# LED_Driver_AREM-80C0.net
KiCad netlist of a schematic drawn in Altium Designer
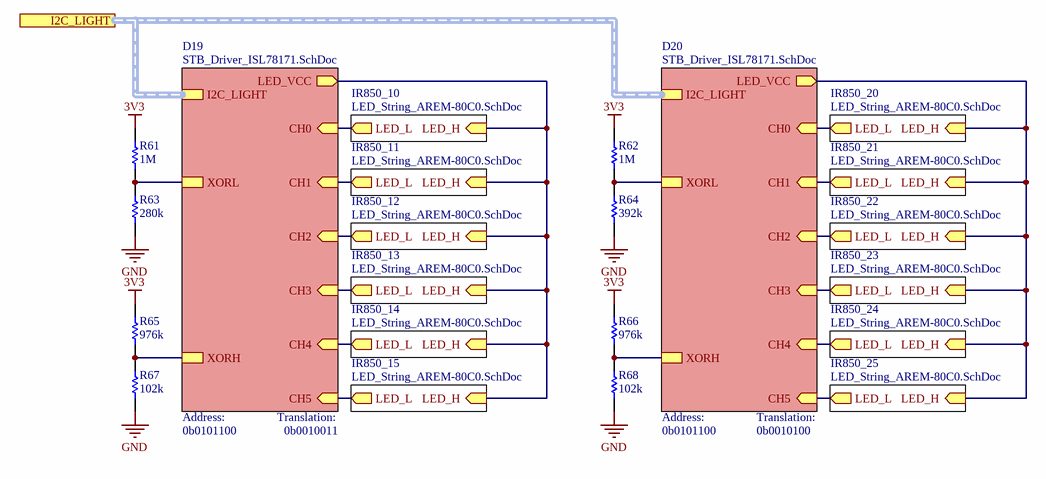
[diagram p0: LED_Driver_AREM-80C0.SchDoc]

(export (version "E")
  (design (tool "Eeschema 10.0.6"))
  (components
    (comp (ref "R61")
      (value "1M")
      (footprint "RESC1005X40X25LL05T05")
      (description "Chip Resistor, 1 MOhm, +/- 1%, 100 mW, -55 to 155 degC, 0402 (1005 Metric), RoHS, Tape and Reel")
      (fields (field (name "PARTNUMBER") "ERJ-2RKF1004X") (field (name "TOLERANCE") "1%"))
      (libsource (lib "Altium Content Vault") (part "RES-2"))
    )
    (comp (ref "R62")
      (value "1M")
      (footprint "RESC1005X40X25LL05T05")
      (description "Chip Resistor, 1 MOhm, +/- 1%, 100 mW, -55 to 155 degC, 0402 (1005 Metric), RoHS, Tape and Reel")
      (fields (field (name "PARTNUMBER") "ERJ-2RKF1004X") (field (name "TOLERANCE") "1%"))
      (libsource (lib "Altium Content Vault") (part "RES-2"))
    )
    (comp (ref "R63")
      (value "280k")
      (footprint "RESC1005X40X25LL05T05")
      (description "Chip Resistor, 280 KOhm, +/- 1%, 100 mW, -55 to 155 degC, 0402 (1005 Metric), RoHS, Cut Tape")
      (fields (field (name "PARTNUMBER") "ERJ-2RKF2803X") (field (name "MANUFACTURER") "Basic Passives"))
      (libsource (lib "Altium Content Vault") (part "RES-2"))
    )
    (comp (ref "R64")
      (value "392k")
      (footprint "RESC1005X40X25LL05T05")
      (fields
        (field (name "PART NUMBER") "ERJ-2RKF3923X")
        (field (name "MANUFACTURER") "Panasonic")
        (field (name "TOLERANCE") "1%")
      )
      (libsource (lib "Altium Content Vault") (part "RES"))
    )
    (comp (ref "R65")
      (value "976k")
      (footprint "RESC1005X40X25LL05T05")
      (fields
        (field (name "MANUFACTURER") "Panasonic")
        (field (name "PART NUMBER") "ERJ-2RKF9763X")
        (field (name "TOLERANCE") "1%")
      )
      (libsource (lib "Altium Content Vault") (part "RES"))
    )
    (comp (ref "R66")
      (value "976k")
      (footprint "RESC1005X40X25LL05T05")
      (fields
        (field (name "MANUFACTURER") "Panasonic")
        (field (name "PART NUMBER") "ERJ-2RKF9763X")
        (field (name "TOLERANCE") "1%")
      )
      (libsource (lib "Altium Content Vault") (part "RES"))
    )
    (comp (ref "R67")
      (value "102k")
      (footprint "RESC1005X40X25LL05T05")
      (fields
        (field (name "MANUFACTURER") "Panasonic")
        (field (name "PART NUMBER") "ERJ-2RKF1023X")
        (field (name "TOLERANCE") "1%")
      )
      (libsource (lib "Altium Content Vault") (part "RES"))
    )
    (comp (ref "R68")
      (value "102k")
      (footprint "RESC1005X40X25LL05T05")
      (fields
        (field (name "MANUFACTURER") "Panasonic")
        (field (name "PART NUMBER") "ERJ-2RKF1023X")
        (field (name "TOLERANCE") "1%")
      )
      (libsource (lib "Altium Content Vault") (part "RES"))
    )
  )
  (nets
    (net (code "17") (name "/XORH") (class "Default")
      (node (ref "R66") (pin "1") (pinfunction "1_1") (pintype "passive"))
      (node (ref "R68") (pin "2") (pinfunction "2_2") (pintype "passive"))
    )
    (net (code "18") (name "/XORH_1") (class "Default")
      (node (ref "R65") (pin "1") (pinfunction "1_1") (pintype "passive"))
      (node (ref "R67") (pin "2") (pinfunction "2_2") (pintype "passive"))
    )
    (net (code "19") (name "/XORL") (class "Default")
      (node (ref "R62") (pin "1") (pinfunction "1_1") (pintype "passive"))
      (node (ref "R64") (pin "2") (pinfunction "2_2") (pintype "passive"))
    )
    (net (code "20") (name "/XORL_1") (class "Default")
      (node (ref "R61") (pin "1") (pinfunction "1_1") (pintype "passive"))
      (node (ref "R63") (pin "2") (pinfunction "2_2") (pintype "passive"))
    )
    (net (code "21") (name "3V3") (class "Default")
      (node (ref "R61") (pin "2") (pinfunction "2_2") (pintype "passive"))
      (node (ref "R62") (pin "2") (pinfunction "2_2") (pintype "passive"))
      (node (ref "R65") (pin "2") (pinfunction "2_2") (pintype "passive"))
      (node (ref "R66") (pin "2") (pinfunction "2_2") (pintype "passive"))
    )
    (net (code "22") (name "GND") (class "Default")
      (node (ref "R63") (pin "1") (pinfunction "1_1") (pintype "passive"))
      (node (ref "R64") (pin "1") (pinfunction "1_1") (pintype "passive"))
      (node (ref "R67") (pin "1") (pinfunction "1_1") (pintype "passive"))
      (node (ref "R68") (pin "1") (pinfunction "1_1") (pintype "passive"))
    )
  )
)
